# Bus_Stop_Kiosk_Rev_1.net
KiCad netlist of a schematic drawn in EAGLE
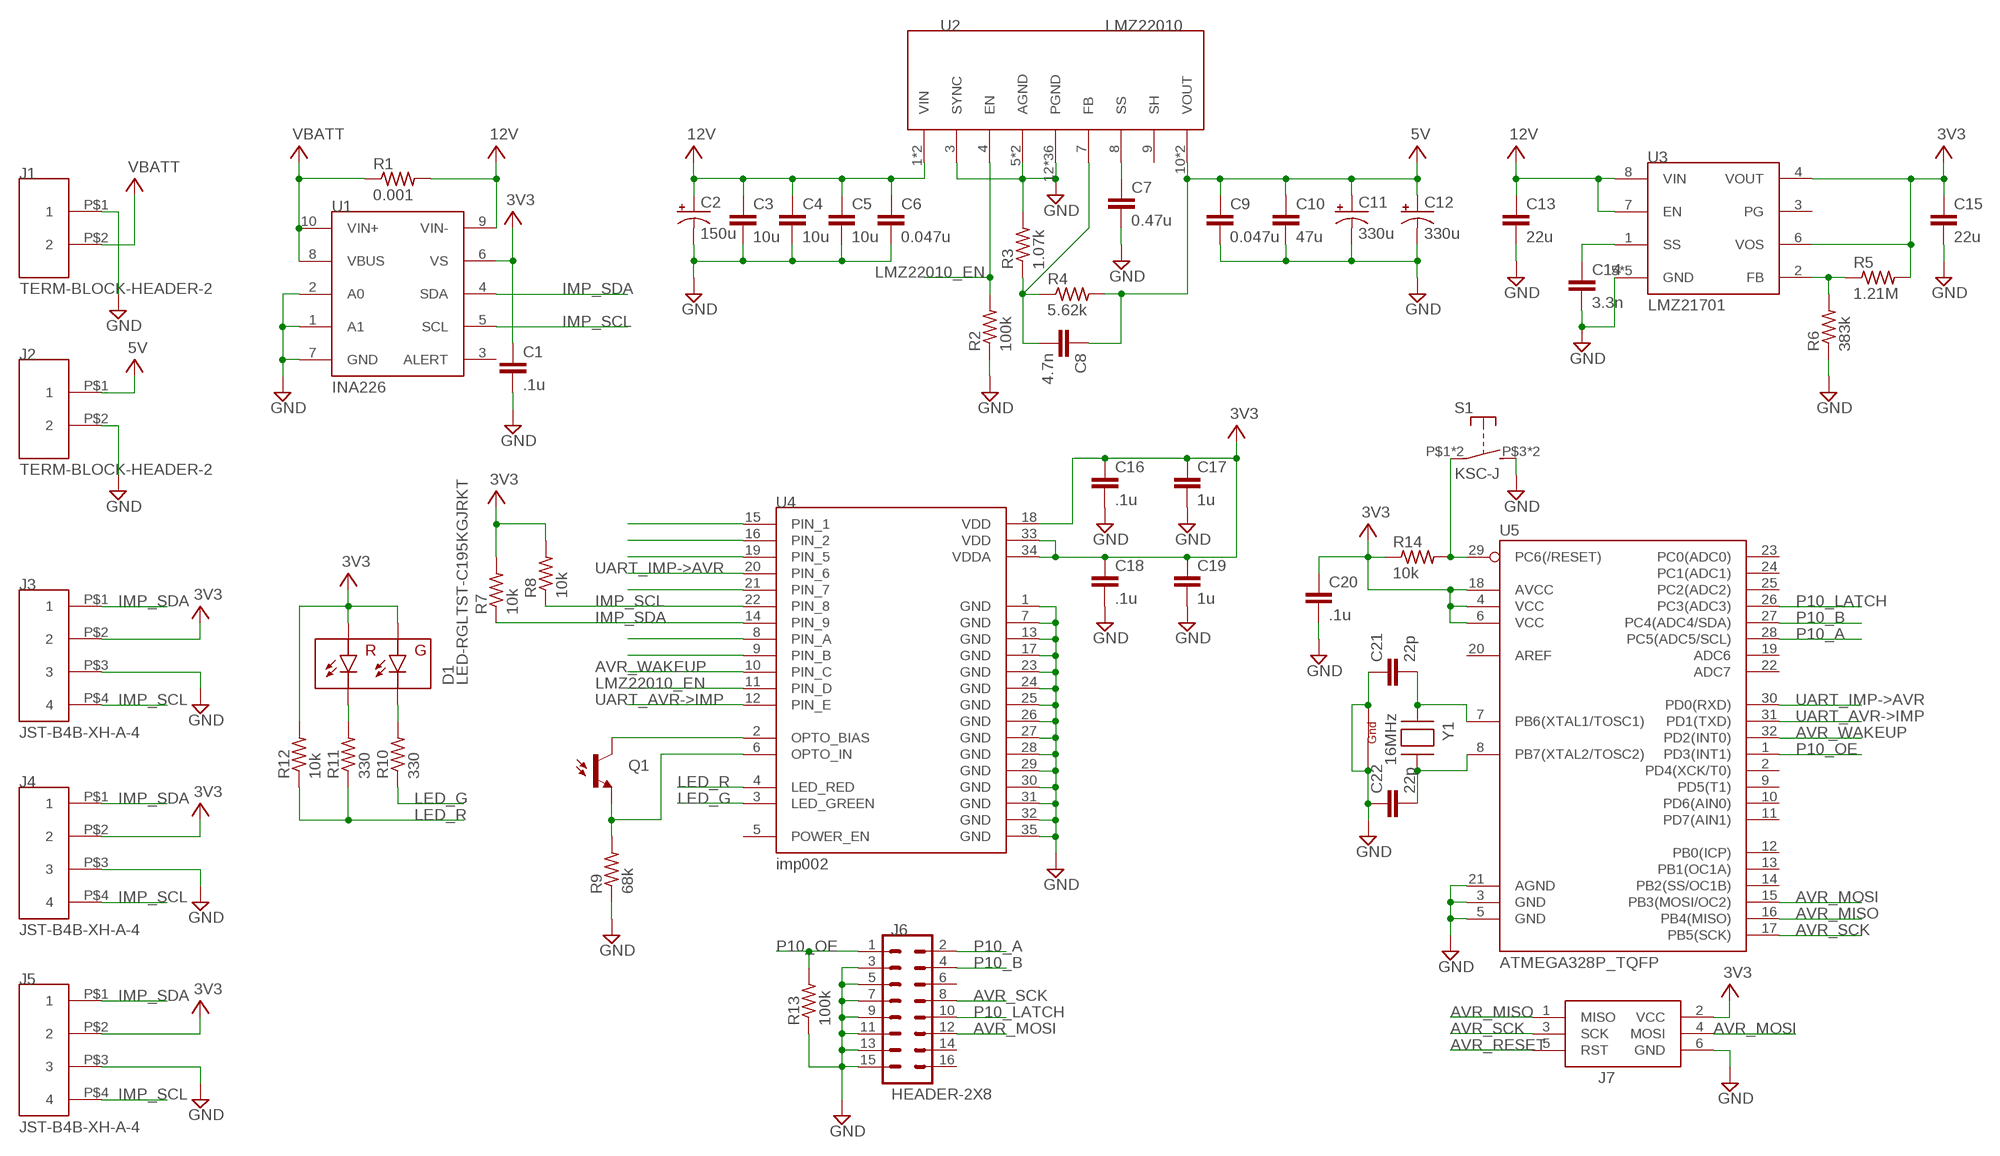
[diagram p0: schematic, sheet 1]

(export (version "E")
  (design (tool "Eeschema 10.0.6"))
  (components
    (comp (ref "C1")
      (value ".1u")
      (footprint "eagle-import:C0603K")
      (libsource (lib "eagle-import") (part "C-EUC0603K"))
    )
    (comp (ref "C2")
      (value "150u")
      (footprint "eagle-import:PANASONIC_G")
      (libsource (lib "eagle-import") (part "CAP_POLG"))
    )
    (comp (ref "C3")
      (value "10u")
      (footprint "eagle-import:C1210K")
      (libsource (lib "eagle-import") (part "C-EUC1210K"))
    )
    (comp (ref "C4")
      (value "10u")
      (footprint "eagle-import:C1210K")
      (libsource (lib "eagle-import") (part "C-EUC1210K"))
    )
    (comp (ref "C5")
      (value "10u")
      (footprint "eagle-import:C1210K")
      (libsource (lib "eagle-import") (part "C-EUC1210K"))
    )
    (comp (ref "C6")
      (value "0.047u")
      (footprint "eagle-import:C1206K")
      (libsource (lib "eagle-import") (part "C-EUC1206K"))
    )
    (comp (ref "C7")
      (value "0.47u")
      (footprint "eagle-import:C0603K")
      (libsource (lib "eagle-import") (part "C-EUC0603K"))
    )
    (comp (ref "C8")
      (value "4.7n")
      (footprint "eagle-import:C0603K")
      (libsource (lib "eagle-import") (part "C-EUC0603K"))
    )
    (comp (ref "C9")
      (value "0.047u")
      (footprint "eagle-import:C1206K")
      (libsource (lib "eagle-import") (part "C-EUC1206K"))
    )
    (comp (ref "C10")
      (value "47u")
      (footprint "eagle-import:C1210K")
      (libsource (lib "eagle-import") (part "C-EUC1210K"))
    )
    (comp (ref "C11")
      (value "330u")
      (footprint "eagle-import:EIA7343")
      (libsource (lib "eagle-import") (part "CAP_POL7343"))
    )
    (comp (ref "C12")
      (value "330u")
      (footprint "eagle-import:EIA7343")
      (libsource (lib "eagle-import") (part "CAP_POL7343"))
    )
    (comp (ref "C13")
      (value "22u")
      (footprint "eagle-import:C1210K")
      (libsource (lib "eagle-import") (part "C-EUC1210K"))
    )
    (comp (ref "C14")
      (value "3.3n")
      (footprint "eagle-import:C0603K")
      (libsource (lib "eagle-import") (part "C-EUC0603K"))
    )
    (comp (ref "C15")
      (value "22u")
      (footprint "eagle-import:C0805K")
      (libsource (lib "eagle-import") (part "C-EUC0805K"))
    )
    (comp (ref "C16")
      (value ".1u")
      (footprint "eagle-import:C0603K")
      (libsource (lib "eagle-import") (part "C-EUC0603K"))
    )
    (comp (ref "C17")
      (value "1u")
      (footprint "eagle-import:C0603K")
      (libsource (lib "eagle-import") (part "C-EUC0603K"))
    )
    (comp (ref "C18")
      (value ".1u")
      (footprint "eagle-import:C0603K")
      (libsource (lib "eagle-import") (part "C-EUC0603K"))
    )
    (comp (ref "C19")
      (value "1u")
      (footprint "eagle-import:C0603K")
      (libsource (lib "eagle-import") (part "C-EUC0603K"))
    )
    (comp (ref "C20")
      (value ".1u")
      (footprint "eagle-import:C0603K")
      (libsource (lib "eagle-import") (part "C-EUC0603K"))
    )
    (comp (ref "C21")
      (value "22p")
      (footprint "eagle-import:C0603K")
      (libsource (lib "eagle-import") (part "C-EUC0603K"))
    )
    (comp (ref "C22")
      (value "22p")
      (footprint "eagle-import:C0603K")
      (libsource (lib "eagle-import") (part "C-EUC0603K"))
    )
    (comp (ref "D1")
      (value "LED-RGLTST-C195KGJRKT")
      (footprint "eagle-import:LTST-C195KGJRKT")
      (libsource (lib "eagle-import") (part "LED-RGLTST-C195KGJRKT"))
    )
    (comp (ref "J1")
      (value "TERM-BLOCK-HEADER-2")
      (footprint "eagle-import:TERM-BLOCK-HDR-2")
      (libsource (lib "eagle-import") (part "TERM-BLOCK-HEADER-2"))
    )
    (comp (ref "J2")
      (value "TERM-BLOCK-HEADER-2")
      (footprint "eagle-import:TERM-BLOCK-HDR-2")
      (libsource (lib "eagle-import") (part "TERM-BLOCK-HEADER-2"))
    )
    (comp (ref "J3")
      (value "JST-B4B-XH-A-4")
      (footprint "eagle-import:JST-B4B-XH-A-4")
      (libsource (lib "eagle-import") (part "JST-B4B-XH-A-4"))
    )
    (comp (ref "J4")
      (value "JST-B4B-XH-A-4")
      (footprint "eagle-import:JST-B4B-XH-A-4")
      (libsource (lib "eagle-import") (part "JST-B4B-XH-A-4"))
    )
    (comp (ref "J5")
      (value "JST-B4B-XH-A-4")
      (footprint "eagle-import:JST-B4B-XH-A-4")
      (libsource (lib "eagle-import") (part "JST-B4B-XH-A-4"))
    )
    (comp (ref "J6")
      (value "HEADER-2X8")
      (footprint "eagle-import:HEADER-2X8-SHROUDED")
      (libsource (lib "eagle-import") (part "HEADER-2X8"))
    )
    (comp (ref "J7")
      (value "AVRISP-6")
      (footprint "eagle-import:AVRISP")
      (libsource (lib "eagle-import") (part "AVRISP-6"))
    )
    (comp (ref "Q1")
      (value "PHOTOTRANSISTORPT17-21C-L41-TR8")
      (footprint "eagle-import:PT17-21C-L41-TR8")
      (libsource (lib "eagle-import") (part "PHOTOTRANSISTORPT17-21C-L41-TR8"))
    )
    (comp (ref "R1")
      (value "0.001")
      (footprint "eagle-import:R1206")
      (libsource (lib "eagle-import") (part "R-US_R1206"))
    )
    (comp (ref "R2")
      (value "100k")
      (footprint "eagle-import:R0603")
      (libsource (lib "eagle-import") (part "R-US_R0603"))
    )
    (comp (ref "R3")
      (value "1.07k")
      (footprint "eagle-import:R0603")
      (libsource (lib "eagle-import") (part "R-US_R0603"))
    )
    (comp (ref "R4")
      (value "5.62k")
      (footprint "eagle-import:R0603")
      (libsource (lib "eagle-import") (part "R-US_R0603"))
    )
    (comp (ref "R5")
      (value "1.21M")
      (footprint "eagle-import:R0603")
      (libsource (lib "eagle-import") (part "R-US_R0603"))
    )
    (comp (ref "R6")
      (value "383k")
      (footprint "eagle-import:R0603")
      (libsource (lib "eagle-import") (part "R-US_R0603"))
    )
    (comp (ref "R7")
      (value "10k")
      (footprint "eagle-import:R0603")
      (libsource (lib "eagle-import") (part "R-US_R0603"))
    )
    (comp (ref "R8")
      (value "10k")
      (footprint "eagle-import:R0603")
      (libsource (lib "eagle-import") (part "R-US_R0603"))
    )
    (comp (ref "R9")
      (value "68k")
      (footprint "eagle-import:R0603")
      (libsource (lib "eagle-import") (part "R-US_R0603"))
    )
    (comp (ref "R10")
      (value "330")
      (footprint "eagle-import:R0603")
      (libsource (lib "eagle-import") (part "R-US_R0603"))
    )
    (comp (ref "R11")
      (value "330")
      (footprint "eagle-import:R0603")
      (libsource (lib "eagle-import") (part "R-US_R0603"))
    )
    (comp (ref "R12")
      (value "10k")
      (footprint "eagle-import:R0603")
      (libsource (lib "eagle-import") (part "R-US_R0603"))
    )
    (comp (ref "R13")
      (value "100k")
      (footprint "eagle-import:R0603")
      (libsource (lib "eagle-import") (part "R-US_R0603"))
    )
    (comp (ref "R14")
      (value "10k")
      (footprint "eagle-import:R0603")
      (libsource (lib "eagle-import") (part "R-US_R0603"))
    )
    (comp (ref "S1")
      (value "KSC-J")
      (footprint "eagle-import:C&K-KSC")
      (libsource (lib "eagle-import") (part "KSC-J"))
    )
    (comp (ref "U1")
      (value "INA226")
      (footprint "eagle-import:VSSOP-10")
      (libsource (lib "eagle-import") (part "INA226"))
    )
    (comp (ref "U2")
      (value "LMZ22010")
      (footprint "eagle-import:TO-PMOD-11")
      (libsource (lib "eagle-import") (part "LMZ22010"))
    )
    (comp (ref "U3")
      (value "LMZ21701")
      (footprint "eagle-import:SIL0008E")
      (libsource (lib "eagle-import") (part "LMZ21701"))
    )
    (comp (ref "U4")
      (value "imp002")
      (footprint "eagle-import:ELECTRIC_IMP_IMP002")
      (libsource (lib "eagle-import") (part "ELECTRIC_IMP_IMP002"))
    )
    (comp (ref "U5")
      (value "ATMEGA328P_TQFP")
      (footprint "eagle-import:TQFP32-08")
      (libsource (lib "eagle-import") (part "ATMEGA328P_TQFP"))
    )
    (comp (ref "Y1")
      (value "16MHz")
      (footprint "eagle-import:NX3225")
      (libsource (lib "eagle-import") (part "XTAL-4-3225"))
    )
  )
  (nets
    (net (code "1") (name "/AVR_MISO") (class "Default")
      (node (ref "J7") (pin "1") (pinfunction "MISO_1") (pintype "input"))
      (node (ref "U5") (pin "16") (pinfunction "PB4(MISO)_16") (pintype "bidirectional"))
    )
    (net (code "2") (name "/AVR_MOSI") (class "Default")
      (node (ref "J6") (pin "12") (pinfunction "12_12") (pintype "passive"))
      (node (ref "J7") (pin "4") (pinfunction "MOSI_4") (pintype "output"))
      (node (ref "U5") (pin "15") (pinfunction "PB3(MOSI/OC2)_15") (pintype "bidirectional"))
    )
    (net (code "3") (name "/AVR_RESET") (class "Default")
      (node (ref "J7") (pin "5") (pinfunction "RST_5") (pintype "output"))
      (node (ref "R14") (pin "2") (pinfunction "2_2") (pintype "passive"))
      (node (ref "S1") (pin "P$1") (pinfunction "P_P$1") (pintype "passive"))
      (node (ref "S1") (pin "P$2") (pinfunction "P_P$2") (pintype "passive"))
      (node (ref "U5") (pin "29") (pinfunction "PC6(/RESET)_29") (pintype "bidirectional"))
    )
    (net (code "4") (name "/AVR_SCK") (class "Default")
      (node (ref "J6") (pin "8") (pinfunction "8_8") (pintype "passive"))
      (node (ref "J7") (pin "3") (pinfunction "SCK_3") (pintype "output"))
      (node (ref "U5") (pin "17") (pinfunction "PB5(SCK)_17") (pintype "bidirectional"))
    )
    (net (code "5") (name "/AVR_WAKEUP") (class "Default")
      (node (ref "U4") (pin "10") (pinfunction "PIN_C_10") (pintype "bidirectional"))
      (node (ref "U5") (pin "32") (pinfunction "PD2(INT0)_32") (pintype "bidirectional"))
    )
    (net (code "6") (name "/IMP_SCL") (class "Default")
      (node (ref "J3") (pin "P$4") (pinfunction "4_P$4") (pintype "bidirectional"))
      (node (ref "J4") (pin "P$4") (pinfunction "4_P$4") (pintype "bidirectional"))
      (node (ref "J5") (pin "P$4") (pinfunction "4_P$4") (pintype "bidirectional"))
      (node (ref "R8") (pin "1") (pinfunction "1_1") (pintype "passive"))
      (node (ref "U1") (pin "5") (pinfunction "SCL_5") (pintype "bidirectional"))
      (node (ref "U4") (pin "22") (pinfunction "PIN_8_22") (pintype "bidirectional"))
    )
    (net (code "7") (name "/IMP_SDA") (class "Default")
      (node (ref "J3") (pin "P$1") (pinfunction "1_P$1") (pintype "bidirectional"))
      (node (ref "J4") (pin "P$1") (pinfunction "1_P$1") (pintype "bidirectional"))
      (node (ref "J5") (pin "P$1") (pinfunction "1_P$1") (pintype "bidirectional"))
      (node (ref "R7") (pin "1") (pinfunction "1_1") (pintype "passive"))
      (node (ref "U1") (pin "4") (pinfunction "SDA_4") (pintype "bidirectional"))
      (node (ref "U4") (pin "14") (pinfunction "PIN_9_14") (pintype "bidirectional"))
    )
    (net (code "8") (name "/LED_G") (class "Default")
      (node (ref "R10") (pin "1") (pinfunction "1_1") (pintype "passive"))
      (node (ref "U4") (pin "3") (pinfunction "LED_GREEN_3") (pintype "bidirectional"))
    )
    (net (code "9") (name "/LED_R") (class "Default")
      (node (ref "R11") (pin "1") (pinfunction "1_1") (pintype "passive"))
      (node (ref "R12") (pin "1") (pinfunction "1_1") (pintype "passive"))
      (node (ref "U4") (pin "4") (pinfunction "LED_RED_4") (pintype "bidirectional"))
    )
    (net (code "10") (name "/LMZ22010_EN") (class "Default")
      (node (ref "R2") (pin "2") (pinfunction "2_2") (pintype "passive"))
      (node (ref "U2") (pin "4") (pinfunction "EN_4") (pintype "bidirectional"))
      (node (ref "U4") (pin "11") (pinfunction "PIN_D_11") (pintype "bidirectional"))
    )
    (net (code "11") (name "/P10_A") (class "Default")
      (node (ref "J6") (pin "2") (pinfunction "2_2") (pintype "passive"))
      (node (ref "U5") (pin "28") (pinfunction "PC5(ADC5/SCL)_28") (pintype "bidirectional"))
    )
    (net (code "12") (name "/P10_B") (class "Default")
      (node (ref "J6") (pin "4") (pinfunction "4_4") (pintype "passive"))
      (node (ref "U5") (pin "27") (pinfunction "PC4(ADC4/SDA)_27") (pintype "bidirectional"))
    )
    (net (code "13") (name "/P10_LATCH") (class "Default")
      (node (ref "J6") (pin "10") (pinfunction "10_10") (pintype "passive"))
      (node (ref "U5") (pin "26") (pinfunction "PC3(ADC3)_26") (pintype "bidirectional"))
    )
    (net (code "14") (name "/P10_OE") (class "Default")
      (node (ref "J6") (pin "1") (pinfunction "1_1") (pintype "passive"))
      (node (ref "R13") (pin "2") (pinfunction "2_2") (pintype "passive"))
      (node (ref "U5") (pin "1") (pinfunction "PD3(INT1)_1") (pintype "bidirectional"))
    )
    (net (code "15") (name "/UART_AVR->IMP") (class "Default")
      (node (ref "U4") (pin "12") (pinfunction "PIN_E_12") (pintype "bidirectional"))
      (node (ref "U5") (pin "31") (pinfunction "PD1(TXD)_31") (pintype "bidirectional"))
    )
    (net (code "16") (name "/UART_IMP->AVR") (class "Default")
      (node (ref "U4") (pin "20") (pinfunction "PIN_6_20") (pintype "bidirectional"))
      (node (ref "U5") (pin "30") (pinfunction "PD0(RXD)_30") (pintype "bidirectional"))
    )
    (net (code "17") (name "3V3") (class "Default")
      (node (ref "C1") (pin "1") (pinfunction "1_1") (pintype "passive"))
      (node (ref "C15") (pin "1") (pinfunction "1_1") (pintype "passive"))
      (node (ref "C16") (pin "1") (pinfunction "1_1") (pintype "passive"))
      (node (ref "C17") (pin "1") (pinfunction "1_1") (pintype "passive"))
      (node (ref "C18") (pin "1") (pinfunction "1_1") (pintype "passive"))
      (node (ref "C19") (pin "1") (pinfunction "1_1") (pintype "passive"))
      (node (ref "C20") (pin "1") (pinfunction "1_1") (pintype "passive"))
      (node (ref "D1") (pin "P$1") (pinfunction "GA_P$1") (pintype "passive"))
      (node (ref "D1") (pin "P$2") (pinfunction "RA_P$2") (pintype "passive"))
      (node (ref "J3") (pin "P$2") (pinfunction "2_P$2") (pintype "bidirectional"))
      (node (ref "J4") (pin "P$2") (pinfunction "2_P$2") (pintype "bidirectional"))
      (node (ref "J5") (pin "P$2") (pinfunction "2_P$2") (pintype "bidirectional"))
      (node (ref "J7") (pin "2") (pinfunction "VCC_2") (pintype "power_in"))
      (node (ref "R12") (pin "2") (pinfunction "2_2") (pintype "passive"))
      (node (ref "R14") (pin "1") (pinfunction "1_1") (pintype "passive"))
      (node (ref "R5") (pin "2") (pinfunction "2_2") (pintype "passive"))
      (node (ref "R7") (pin "2") (pinfunction "2_2") (pintype "passive"))
      (node (ref "R8") (pin "2") (pinfunction "2_2") (pintype "passive"))
      (node (ref "U1") (pin "6") (pinfunction "VS_6") (pintype "power_in"))
      (node (ref "U3") (pin "4") (pinfunction "VOUT_4") (pintype "bidirectional"))
      (node (ref "U3") (pin "6") (pinfunction "VOS_6") (pintype "bidirectional"))
      (node (ref "U4") (pin "18") (pinfunction "VDD_18") (pintype "bidirectional"))
      (node (ref "U4") (pin "33") (pinfunction "VDD_33") (pintype "bidirectional"))
      (node (ref "U4") (pin "34") (pinfunction "VDDA_34") (pintype "bidirectional"))
      (node (ref "U5") (pin "18") (pinfunction "AVCC_18") (pintype "bidirectional"))
      (node (ref "U5") (pin "4") (pinfunction "VCC_4") (pintype "bidirectional"))
      (node (ref "U5") (pin "6") (pinfunction "VCC_6") (pintype "bidirectional"))
    )
    (net (code "18") (name "5V") (class "Default")
      (node (ref "C10") (pin "1") (pinfunction "1_1") (pintype "passive"))
      (node (ref "C11") (pin "A") (pinfunction "+_A") (pintype "passive"))
      (node (ref "C12") (pin "A") (pinfunction "+_A") (pintype "passive"))
      (node (ref "C8") (pin "1") (pinfunction "1_1") (pintype "passive"))
      (node (ref "C9") (pin "1") (pinfunction "1_1") (pintype "passive"))
      (node (ref "J2") (pin "P$1") (pinfunction "1_P$1") (pintype "bidirectional"))
      (node (ref "R4") (pin "2") (pinfunction "2_2") (pintype "passive"))
      (node (ref "U2") (pin "10") (pinfunction "VOUT_10") (pintype "bidirectional"))
      (node (ref "U2") (pin "11") (pinfunction "VOUT_11") (pintype "bidirectional"))
    )
    (net (code "19") (name "12V") (class "Default")
      (node (ref "C13") (pin "1") (pinfunction "1_1") (pintype "passive"))
      (node (ref "C2") (pin "+") (pinfunction "+_+") (pintype "passive"))
      (node (ref "C3") (pin "1") (pinfunction "1_1") (pintype "passive"))
      (node (ref "C4") (pin "1") (pinfunction "1_1") (pintype "passive"))
      (node (ref "C5") (pin "1") (pinfunction "1_1") (pintype "passive"))
      (node (ref "C6") (pin "1") (pinfunction "1_1") (pintype "passive"))
      (node (ref "R1") (pin "2") (pinfunction "2_2") (pintype "passive"))
      (node (ref "U1") (pin "9") (pinfunction "VIN-_9") (pintype "bidirectional"))
      (node (ref "U2") (pin "1") (pinfunction "VIN_1") (pintype "bidirectional"))
      (node (ref "U2") (pin "2") (pinfunction "VIN_2") (pintype "bidirectional"))
      (node (ref "U3") (pin "7") (pinfunction "EN_7") (pintype "bidirectional"))
      (node (ref "U3") (pin "8") (pinfunction "VIN_8") (pintype "bidirectional"))
    )
    (net (code "20") (name "GND") (class "Default")
      (node (ref "C1") (pin "2") (pinfunction "2_2") (pintype "passive"))
      (node (ref "C10") (pin "2") (pinfunction "2_2") (pintype "passive"))
      (node (ref "C11") (pin "C") (pinfunction "-_C") (pintype "passive"))
      (node (ref "C12") (pin "C") (pinfunction "-_C") (pintype "passive"))
      (node (ref "C13") (pin "2") (pinfunction "2_2") (pintype "passive"))
      (node (ref "C14") (pin "2") (pinfunction "2_2") (pintype "passive"))
      (node (ref "C15") (pin "2") (pinfunction "2_2") (pintype "passive"))
      (node (ref "C16") (pin "2") (pinfunction "2_2") (pintype "passive"))
      (node (ref "C17") (pin "2") (pinfunction "2_2") (pintype "passive"))
      (node (ref "C18") (pin "2") (pinfunction "2_2") (pintype "passive"))
      (node (ref "C19") (pin "2") (pinfunction "2_2") (pintype "passive"))
      (node (ref "C2") (pin "-") (pinfunction "-_-") (pintype "passive"))
      (node (ref "C20") (pin "2") (pinfunction "2_2") (pintype "passive"))
      (node (ref "C21") (pin "1") (pinfunction "1_1") (pintype "passive"))
      (node (ref "C22") (pin "1") (pinfunction "1_1") (pintype "passive"))
      (node (ref "C3") (pin "2") (pinfunction "2_2") (pintype "passive"))
      (node (ref "C4") (pin "2") (pinfunction "2_2") (pintype "passive"))
      (node (ref "C5") (pin "2") (pinfunction "2_2") (pintype "passive"))
      (node (ref "C6") (pin "2") (pinfunction "2_2") (pintype "passive"))
      (node (ref "C7") (pin "2") (pinfunction "2_2") (pintype "passive"))
      (node (ref "C9") (pin "2") (pinfunction "2_2") (pintype "passive"))
      (node (ref "J1") (pin "P$1") (pinfunction "1_P$1") (pintype "bidirectional"))
      (node (ref "J2") (pin "P$2") (pinfunction "2_P$2") (pintype "bidirectional"))
      (node (ref "J3") (pin "P$3") (pinfunction "3_P$3") (pintype "bidirectional"))
      (node (ref "J4") (pin "P$3") (pinfunction "3_P$3") (pintype "bidirectional"))
      (node (ref "J5") (pin "P$3") (pinfunction "3_P$3") (pintype "bidirectional"))
      (node (ref "J6") (pin "11") (pinfunction "11_11") (pintype "passive"))
      (node (ref "J6") (pin "13") (pinfunction "13_13") (pintype "passive"))
      (node (ref "J6") (pin "15") (pinfunction "15_15") (pintype "passive"))
      (node (ref "J6") (pin "3") (pinfunction "3_3") (pintype "passive"))
      (node (ref "J6") (pin "5") (pinfunction "5_5") (pintype "passive"))
      (node (ref "J6") (pin "7") (pinfunction "7_7") (pintype "passive"))
      (node (ref "J6") (pin "9") (pinfunction "9_9") (pintype "passive"))
      (node (ref "J7") (pin "6") (pinfunction "GND_6") (pintype "power_in"))
      (node (ref "R13") (pin "1") (pinfunction "1_1") (pintype "passive"))
      (node (ref "R2") (pin "1") (pinfunction "1_1") (pintype "passive"))
      (node (ref "R3") (pin "2") (pinfunction "2_2") (pintype "passive"))
      (node (ref "R6") (pin "1") (pinfunction "1_1") (pintype "passive"))
      (node (ref "R9") (pin "1") (pinfunction "1_1") (pintype "passive"))
      (node (ref "S1") (pin "P$3") (pinfunction "S_P$3") (pintype "passive"))
      (node (ref "S1") (pin "P$4") (pinfunction "S_P$4") (pintype "passive"))
      (node (ref "U1") (pin "1") (pinfunction "A1_1") (pintype "bidirectional"))
      (node (ref "U1") (pin "2") (pinfunction "A0_2") (pintype "bidirectional"))
      (node (ref "U1") (pin "7") (pinfunction "GND_7") (pintype "power_in"))
      (node (ref "U2") (pin "12") (pinfunction "PGND_12") (pintype "bidirectional"))
      (node (ref "U2") (pin "3") (pinfunction "SYNC_3") (pintype "bidirectional"))
      (node (ref "U2") (pin "5") (pinfunction "AGND_5") (pintype "bidirectional"))
      (node (ref "U2") (pin "6") (pinfunction "AGND_6") (pintype "bidirectional"))
      (node (ref "U2") (pin "P$1") (pinfunction "PGND_P$1") (pintype "bidirectional"))
      (node (ref "U2") (pin "P$10") (pinfunction "PGND_P$10") (pintype "bidirectional"))
      (node (ref "U2") (pin "P$11") (pinfunction "PGND_P$11") (pintype "bidirectional"))
      (node (ref "U2") (pin "P$12") (pinfunction "PGND_P$12") (pintype "bidirectional"))
      (node (ref "U2") (pin "P$13") (pinfunction "PGND_P$13") (pintype "bidirectional"))
      (node (ref "U2") (pin "P$14") (pinfunction "PGND_P$14") (pintype "bidirectional"))
      (node (ref "U2") (pin "P$15") (pinfunction "PGND_P$15") (pintype "bidirectional"))
      (node (ref "U2") (pin "P$16") (pinfunction "PGND_P$16") (pintype "bidirectional"))
      (node (ref "U2") (pin "P$17") (pinfunction "PGND_P$17") (pintype "bidirectional"))
      (node (ref "U2") (pin "P$18") (pinfunction "PGND_P$18") (pintype "bidirectional"))
      (node (ref "U2") (pin "P$19") (pinfunction "PGND_P$19") (pintype "bidirectional"))
      (node (ref "U2") (pin "P$2") (pinfunction "PGND_P$2") (pintype "bidirectional"))
      (node (ref "U2") (pin "P$20") (pinfunction "PGND_P$20") (pintype "bidirectional"))
      (node (ref "U2") (pin "P$21") (pinfunction "PGND_P$21") (pintype "bidirectional"))
      (node (ref "U2") (pin "P$22") (pinfunction "PGND_P$22") (pintype "bidirectional"))
      (node (ref "U2") (pin "P$23") (pinfunction "PGND_P$23") (pintype "bidirectional"))
      (node (ref "U2") (pin "P$24") (pinfunction "PGND_P$24") (pintype "bidirectional"))
      (node (ref "U2") (pin "P$25") (pinfunction "PGND_P$25") (pintype "bidirectional"))
      (node (ref "U2") (pin "P$26") (pinfunction "PGND_P$26") (pintype "bidirectional"))
      (node (ref "U2") (pin "P$27") (pinfunction "PGND_P$27") (pintype "bidirectional"))
      (node (ref "U2") (pin "P$28") (pinfunction "PGND_P$28") (pintype "bidirectional"))
      (node (ref "U2") (pin "P$29") (pinfunction "PGND_P$29") (pintype "bidirectional"))
      (node (ref "U2") (pin "P$3") (pinfunction "PGND_P$3") (pintype "bidirectional"))
      (node (ref "U2") (pin "P$30") (pinfunction "PGND_P$30") (pintype "bidirectional"))
      (node (ref "U2") (pin "P$31") (pinfunction "PGND_P$31") (pintype "bidirectional"))
      (node (ref "U2") (pin "P$32") (pinfunction "PGND_P$32") (pintype "bidirectional"))
      (node (ref "U2") (pin "P$33") (pinfunction "PGND_P$33") (pintype "bidirectional"))
      (node (ref "U2") (pin "P$34") (pinfunction "PGND_P$34") (pintype "bidirectional"))
      (node (ref "U2") (pin "P$35") (pinfunction "PGND_P$35") (pintype "bidirectional"))
      (node (ref "U2") (pin "P$4") (pinfunction "PGND_P$4") (pintype "bidirectional"))
      (node (ref "U2") (pin "P$5") (pinfunction "PGND_P$5") (pintype "bidirectional"))
      (node (ref "U2") (pin "P$6") (pinfunction "PGND_P$6") (pintype "bidirectional"))
      (node (ref "U2") (pin "P$7") (pinfunction "PGND_P$7") (pintype "bidirectional"))
      (node (ref "U2") (pin "P$8") (pinfunction "PGND_P$8") (pintype "bidirectional"))
      (node (ref "U2") (pin "P$9") (pinfunction "PGND_P$9") (pintype "bidirectional"))
      (node (ref "U3") (pin "10") (pinfunction "GND_10") (pintype "bidirectional"))
      (node (ref "U3") (pin "11") (pinfunction "GND_11") (pintype "bidirectional"))
      (node (ref "U3") (pin "12") (pinfunction "GND_12") (pintype "bidirectional"))
      (node (ref "U3") (pin "5") (pinfunction "GND_5") (pintype "bidirectional"))
      (node (ref "U3") (pin "9") (pinfunction "GND_9") (pintype "bidirectional"))
      (node (ref "U4") (pin "1") (pinfunction "GND_1") (pintype "bidirectional"))
      (node (ref "U4") (pin "13") (pinfunction "GND_13") (pintype "bidirectional"))
      (node (ref "U4") (pin "17") (pinfunction "GND_17") (pintype "bidirectional"))
      (node (ref "U4") (pin "23") (pinfunction "GND_23") (pintype "bidirectional"))
      (node (ref "U4") (pin "24") (pinfunction "GND_24") (pintype "bidirectional"))
      (node (ref "U4") (pin "25") (pinfunction "GND_25") (pintype "bidirectional"))
      (node (ref "U4") (pin "26") (pinfunction "GND_26") (pintype "bidirectional"))
      (node (ref "U4") (pin "27") (pinfunction "GND_27") (pintype "bidirectional"))
      (node (ref "U4") (pin "28") (pinfunction "GND_28") (pintype "bidirectional"))
      (node (ref "U4") (pin "29") (pinfunction "GND_29") (pintype "bidirectional"))
      (node (ref "U4") (pin "30") (pinfunction "GND_30") (pintype "bidirectional"))
      (node (ref "U4") (pin "31") (pinfunction "GND_31") (pintype "bidirectional"))
      (node (ref "U4") (pin "32") (pinfunction "GND_32") (pintype "bidirectional"))
      (node (ref "U4") (pin "35") (pinfunction "GND_35") (pintype "bidirectional"))
      (node (ref "U4") (pin "7") (pinfunction "GND_7") (pintype "bidirectional"))
      (node (ref "U5") (pin "21") (pinfunction "AGND_21") (pintype "bidirectional"))
      (node (ref "U5") (pin "3") (pinfunction "GND_3") (pintype "bidirectional"))
      (node (ref "U5") (pin "5") (pinfunction "GND_5") (pintype "bidirectional"))
      (node (ref "Y1") (pin "2") (pinfunction "G2_2") (pintype "power_in"))
      (node (ref "Y1") (pin "4") (pinfunction "G1_4") (pintype "power_in"))
    )
    (net (code "21") (name "Net-(D1-GC)") (class "Default")
      (node (ref "D1") (pin "P$3") (pinfunction "GC_P$3") (pintype "passive"))
      (node (ref "R10") (pin "2") (pinfunction "2_2") (pintype "passive"))
    )
    (net (code "22") (name "Net-(D1-RC)") (class "Default")
      (node (ref "D1") (pin "P$4") (pinfunction "RC_P$4") (pintype "passive"))
      (node (ref "R11") (pin "2") (pinfunction "2_2") (pintype "passive"))
    )
    (net (code "23") (name "Net-(U2-FB)") (class "Default")
      (node (ref "C8") (pin "2") (pinfunction "2_2") (pintype "passive"))
      (node (ref "R3") (pin "1") (pinfunction "1_1") (pintype "passive"))
      (node (ref "R4") (pin "1") (pinfunction "1_1") (pintype "passive"))
      (node (ref "U2") (pin "7") (pinfunction "FB_7") (pintype "bidirectional"))
    )
    (net (code "24") (name "Net-(U2-SS)") (class "Default")
      (node (ref "C7") (pin "1") (pinfunction "1_1") (pintype "passive"))
      (node (ref "U2") (pin "8") (pinfunction "SS_8") (pintype "bidirectional"))
    )
    (net (code "25") (name "Net-(U3-FB)") (class "Default")
      (node (ref "R5") (pin "1") (pinfunction "1_1") (pintype "passive"))
      (node (ref "R6") (pin "2") (pinfunction "2_2") (pintype "passive"))
      (node (ref "U3") (pin "2") (pinfunction "FB_2") (pintype "bidirectional"))
    )
    (net (code "26") (name "Net-(U3-SS)") (class "Default")
      (node (ref "C14") (pin "1") (pinfunction "1_1") (pintype "passive"))
      (node (ref "U3") (pin "1") (pinfunction "SS_1") (pintype "bidirectional"))
    )
    (net (code "27") (name "Net-(U4-OPTO_BIAS)") (class "Default")
      (node (ref "Q1") (pin "C") (pinfunction "C_C") (pintype "passive"))
      (node (ref "U4") (pin "2") (pinfunction "OPTO_BIAS_2") (pintype "bidirectional"))
    )
    (net (code "28") (name "Net-(U4-OPTO_IN)") (class "Default")
      (node (ref "Q1") (pin "E") (pinfunction "E_E") (pintype "passive"))
      (node (ref "R9") (pin "2") (pinfunction "2_2") (pintype "passive"))
      (node (ref "U4") (pin "6") (pinfunction "OPTO_IN_6") (pintype "bidirectional"))
    )
    (net (code "29") (name "Net-(U5-PB6(XTAL1{slash}TOSC1))") (class "Default")
      (node (ref "C21") (pin "2") (pinfunction "2_2") (pintype "passive"))
      (node (ref "U5") (pin "7") (pinfunction "PB6(XTAL1/TOSC1)_7") (pintype "bidirectional"))
      (node (ref "Y1") (pin "1") (pinfunction "X1_1") (pintype "bidirectional"))
    )
    (net (code "30") (name "Net-(U5-PB7(XTAL2{slash}TOSC2))") (class "Default")
      (node (ref "C22") (pin "2") (pinfunction "2_2") (pintype "passive"))
      (node (ref "U5") (pin "8") (pinfunction "PB7(XTAL2/TOSC2)_8") (pintype "bidirectional"))
      (node (ref "Y1") (pin "3") (pinfunction "X2_3") (pintype "bidirectional"))
    )
    (net (code "31") (name "VBATT") (class "Default")
      (node (ref "J1") (pin "P$2") (pinfunction "2_P$2") (pintype "bidirectional"))
      (node (ref "R1") (pin "1") (pinfunction "1_1") (pintype "passive"))
      (node (ref "U1") (pin "10") (pinfunction "VIN+_10") (pintype "bidirectional"))
      (node (ref "U1") (pin "8") (pinfunction "VBUS_8") (pintype "power_in"))
    )
    (net (code "32") (name "unconnected-(J6-Pad6)") (class "Default")
      (node (ref "J6") (pin "6") (pinfunction "6_6") (pintype "passive"))
    )
    (net (code "33") (name "unconnected-(J6-Pad14)") (class "Default")
      (node (ref "J6") (pin "14") (pinfunction "14_14") (pintype "passive"))
    )
    (net (code "34") (name "unconnected-(J6-Pad16)") (class "Default")
      (node (ref "J6") (pin "16") (pinfunction "16_16") (pintype "passive"))
    )
    (net (code "35") (name "unconnected-(U1-ALERT-Pad3)") (class "Default")
      (node (ref "U1") (pin "3") (pinfunction "ALERT_3") (pintype "bidirectional"))
    )
    (net (code "36") (name "unconnected-(U2-SH-Pad9)") (class "Default")
      (node (ref "U2") (pin "9") (pinfunction "SH_9") (pintype "bidirectional"))
    )
    (net (code "37") (name "unconnected-(U3-PG-Pad3)") (class "Default")
      (node (ref "U3") (pin "3") (pinfunction "PG_3") (pintype "bidirectional"))
    )
    (net (code "38") (name "unconnected-(U4-PIN_1-Pad15)") (class "Default")
      (node (ref "U4") (pin "15") (pinfunction "PIN_1_15") (pintype "bidirectional"))
    )
    (net (code "39") (name "unconnected-(U4-PIN_2-Pad16)") (class "Default")
      (node (ref "U4") (pin "16") (pinfunction "PIN_2_16") (pintype "bidirectional"))
    )
    (net (code "40") (name "unconnected-(U4-PIN_5-Pad19)") (class "Default")
      (node (ref "U4") (pin "19") (pinfunction "PIN_5_19") (pintype "bidirectional"))
    )
    (net (code "41") (name "unconnected-(U4-PIN_7-Pad21)") (class "Default")
      (node (ref "U4") (pin "21") (pinfunction "PIN_7_21") (pintype "bidirectional"))
    )
    (net (code "42") (name "unconnected-(U4-PIN_A-Pad8)") (class "Default")
      (node (ref "U4") (pin "8") (pinfunction "PIN_A_8") (pintype "bidirectional"))
    )
    (net (code "43") (name "unconnected-(U4-PIN_B-Pad9)") (class "Default")
      (node (ref "U4") (pin "9") (pinfunction "PIN_B_9") (pintype "bidirectional"))
    )
    (net (code "44") (name "unconnected-(U4-POWER_EN-Pad5)") (class "Default")
      (node (ref "U4") (pin "5") (pinfunction "POWER_EN_5") (pintype "bidirectional"))
    )
    (net (code "45") (name "unconnected-(U5-ADC6-Pad19)") (class "Default")
      (node (ref "U5") (pin "19") (pinfunction "ADC6_19") (pintype "bidirectional"))
    )
    (net (code "46") (name "unconnected-(U5-ADC7-Pad22)") (class "Default")
      (node (ref "U5") (pin "22") (pinfunction "ADC7_22") (pintype "bidirectional"))
    )
    (net (code "47") (name "unconnected-(U5-AREF-Pad20)") (class "Default")
      (node (ref "U5") (pin "20") (pinfunction "AREF_20") (pintype "bidirectional"))
    )
    (net (code "48") (name "unconnected-(U5-PB0(ICP)-Pad12)") (class "Default")
      (node (ref "U5") (pin "12") (pinfunction "PB0(ICP)_12") (pintype "bidirectional"))
    )
    (net (code "49") (name "unconnected-(U5-PB1(OC1A)-Pad13)") (class "Default")
      (node (ref "U5") (pin "13") (pinfunction "PB1(OC1A)_13") (pintype "bidirectional"))
    )
    (net (code "50") (name "unconnected-(U5-PB2(SS{slash}OC1B)-Pad14)") (class "Default")
      (node (ref "U5") (pin "14") (pinfunction "PB2(SS/OC1B)_14") (pintype "bidirectional"))
    )
    (net (code "51") (name "unconnected-(U5-PC0(ADC0)-Pad23)") (class "Default")
      (node (ref "U5") (pin "23") (pinfunction "PC0(ADC0)_23") (pintype "bidirectional"))
    )
    (net (code "52") (name "unconnected-(U5-PC1(ADC1)-Pad24)") (class "Default")
      (node (ref "U5") (pin "24") (pinfunction "PC1(ADC1)_24") (pintype "bidirectional"))
    )
    (net (code "53") (name "unconnected-(U5-PC2(ADC2)-Pad25)") (class "Default")
      (node (ref "U5") (pin "25") (pinfunction "PC2(ADC2)_25") (pintype "bidirectional"))
    )
    (net (code "54") (name "unconnected-(U5-PD4(XCK{slash}T0)-Pad2)") (class "Default")
      (node (ref "U5") (pin "2") (pinfunction "PD4(XCK/T0)_2") (pintype "bidirectional"))
    )
    (net (code "55") (name "unconnected-(U5-PD5(T1)-Pad9)") (class "Default")
      (node (ref "U5") (pin "9") (pinfunction "PD5(T1)_9") (pintype "bidirectional"))
    )
    (net (code "56") (name "unconnected-(U5-PD6(AIN0)-Pad10)") (class "Default")
      (node (ref "U5") (pin "10") (pinfunction "PD6(AIN0)_10") (pintype "bidirectional"))
    )
    (net (code "57") (name "unconnected-(U5-PD7(AIN1)-Pad11)") (class "Default")
      (node (ref "U5") (pin "11") (pinfunction "PD7(AIN1)_11") (pintype "bidirectional"))
    )
  )
)
